# xmastree.net
KiCad netlist of a schematic drawn in EAGLE
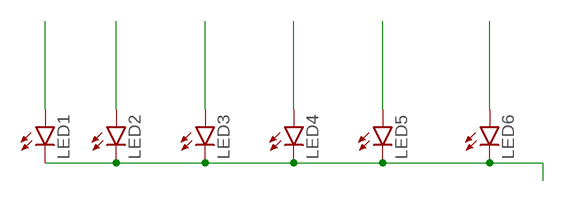
[diagram p0: schematic, sheet 1]

(export (version "E")
  (design (tool "Eeschema 10.0.6"))
  (components
    (comp (ref "LED1")
      (value "LED3MM")
      (footprint "eagle-import:LED3MM")
      (libsource (lib "eagle-import") (part "LED3MM"))
    )
    (comp (ref "LED2")
      (value "LED3MM")
      (footprint "eagle-import:LED3MM")
      (libsource (lib "eagle-import") (part "LED3MM"))
    )
    (comp (ref "LED3")
      (value "LED3MM")
      (footprint "eagle-import:LED3MM")
      (libsource (lib "eagle-import") (part "LED3MM"))
    )
    (comp (ref "LED4")
      (value "LED3MM")
      (footprint "eagle-import:LED3MM")
      (libsource (lib "eagle-import") (part "LED3MM"))
    )
    (comp (ref "LED5")
      (value "LED3MM")
      (footprint "eagle-import:LED3MM")
      (libsource (lib "eagle-import") (part "LED3MM"))
    )
    (comp (ref "LED6")
      (value "LED3MM")
      (footprint "eagle-import:LED3MM")
      (libsource (lib "eagle-import") (part "LED3MM"))
    )
  )
  (nets
    (net (code "1") (name "Net-(LED1-C)") (class "Default")
      (node (ref "LED1") (pin "K") (pinfunction "C_K") (pintype "passive"))
      (node (ref "LED2") (pin "K") (pinfunction "C_K") (pintype "passive"))
      (node (ref "LED3") (pin "K") (pinfunction "C_K") (pintype "passive"))
      (node (ref "LED4") (pin "K") (pinfunction "C_K") (pintype "passive"))
      (node (ref "LED5") (pin "K") (pinfunction "C_K") (pintype "passive"))
      (node (ref "LED6") (pin "K") (pinfunction "C_K") (pintype "passive"))
    )
    (net (code "2") (name "unconnected-(LED1-PadA)") (class "Default")
      (node (ref "LED1") (pin "A") (pinfunction "A_A") (pintype "passive"))
    )
    (net (code "3") (name "unconnected-(LED2-PadA)") (class "Default")
      (node (ref "LED2") (pin "A") (pinfunction "A_A") (pintype "passive"))
    )
    (net (code "4") (name "unconnected-(LED3-PadA)") (class "Default")
      (node (ref "LED3") (pin "A") (pinfunction "A_A") (pintype "passive"))
    )
    (net (code "5") (name "unconnected-(LED4-PadA)") (class "Default")
      (node (ref "LED4") (pin "A") (pinfunction "A_A") (pintype "passive"))
    )
    (net (code "6") (name "unconnected-(LED5-PadA)") (class "Default")
      (node (ref "LED5") (pin "A") (pinfunction "A_A") (pintype "passive"))
    )
    (net (code "7") (name "unconnected-(LED6-PadA)") (class "Default")
      (node (ref "LED6") (pin "A") (pinfunction "A_A") (pintype "passive"))
    )
  )
)
